# barGraph.net
KiCad netlist of a schematic drawn in Altium Designer
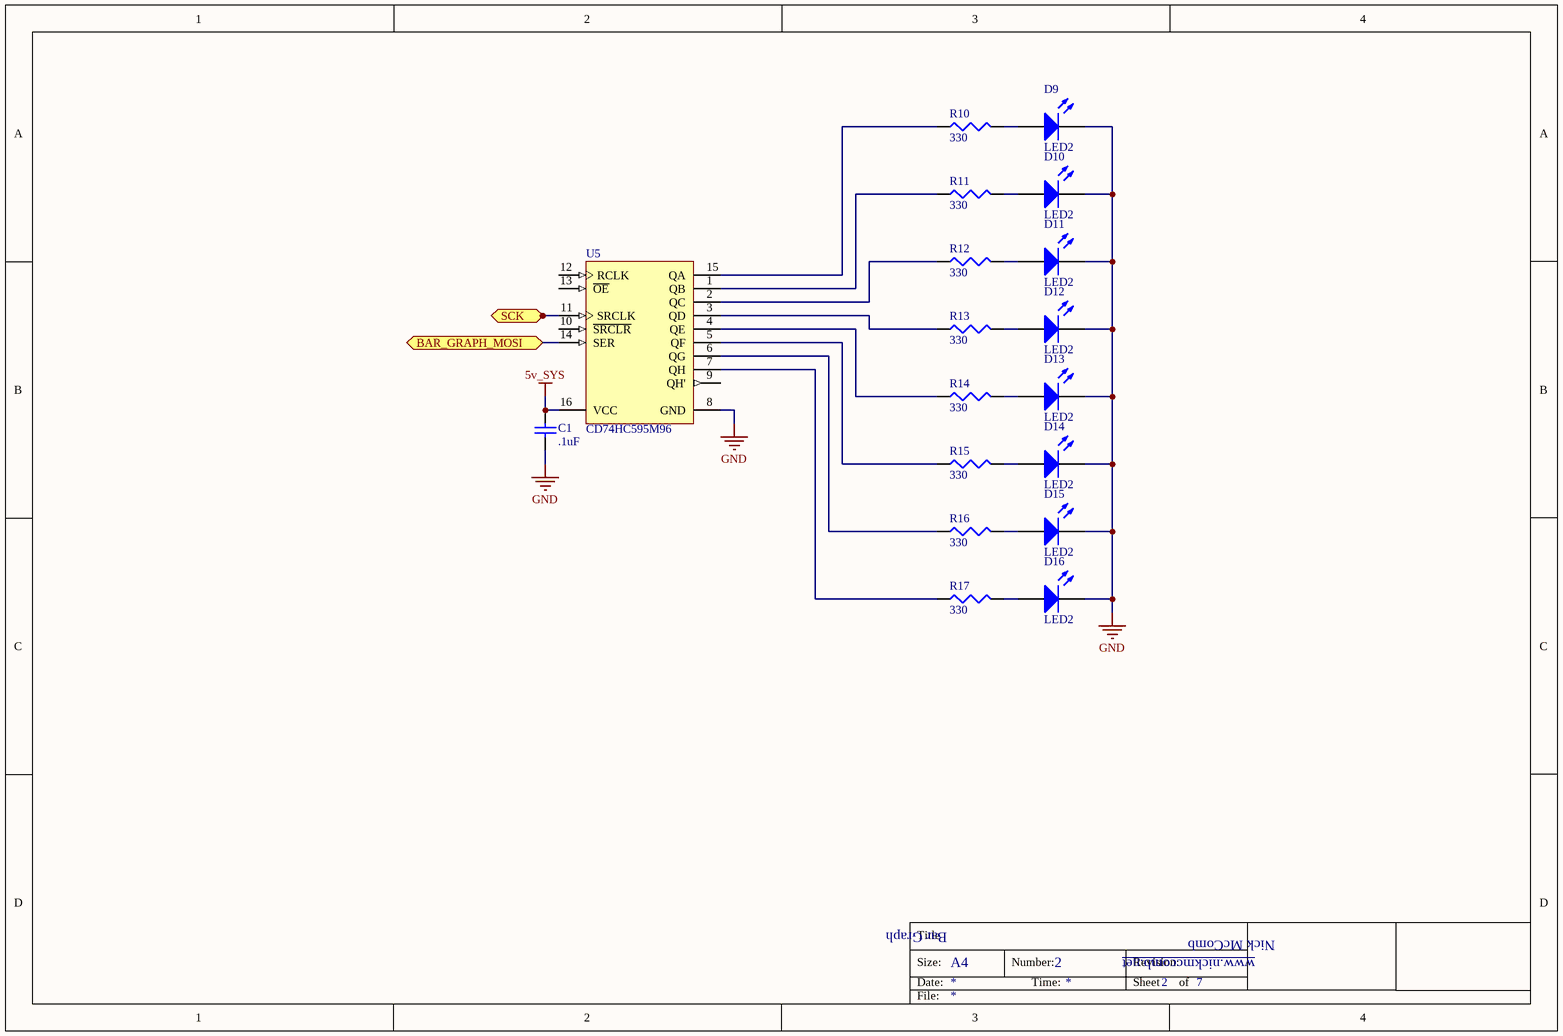
[diagram p0: barGraph.SchDoc]

(export (version "E")
  (design (tool "Eeschema 10.0.6"))
  (components
    (comp (ref "C1")
      (value ".1uF")
      (footprint "C0805")
      (description "Capacitor")
      (fields (field (name "Comment") "0805 style, by default") (field (name "PUBLISHER") "Altium Limited"))
      (libsource (lib "lab2") (part "Cap"))
    )
    (comp (ref "D9")
      (value "LED2")
      (footprint "basic_led")
      (description "Typical RED, GREEN, YELLOW, AMBER GaAs LED")
      (fields (field (name "PUBLISHER") "Altium Limited"))
      (libsource (lib "lab2") (part "LED2"))
    )
    (comp (ref "D10")
      (value "LED2")
      (footprint "basic_led")
      (description "Typical RED, GREEN, YELLOW, AMBER GaAs LED")
      (fields (field (name "PUBLISHER") "Altium Limited"))
      (libsource (lib "lab2") (part "LED2"))
    )
    (comp (ref "D11")
      (value "LED2")
      (footprint "basic_led")
      (description "Typical RED, GREEN, YELLOW, AMBER GaAs LED")
      (fields (field (name "PUBLISHER") "Altium Limited"))
      (libsource (lib "lab2") (part "LED2"))
    )
    (comp (ref "D12")
      (value "LED2")
      (footprint "basic_led")
      (description "Typical RED, GREEN, YELLOW, AMBER GaAs LED")
      (fields (field (name "PUBLISHER") "Altium Limited"))
      (libsource (lib "lab2") (part "LED2"))
    )
    (comp (ref "D13")
      (value "LED2")
      (footprint "basic_led")
      (description "Typical RED, GREEN, YELLOW, AMBER GaAs LED")
      (fields (field (name "PUBLISHER") "Altium Limited"))
      (libsource (lib "lab2") (part "LED2"))
    )
    (comp (ref "D14")
      (value "LED2")
      (footprint "basic_led")
      (description "Typical RED, GREEN, YELLOW, AMBER GaAs LED")
      (fields (field (name "PUBLISHER") "Altium Limited"))
      (libsource (lib "lab2") (part "LED2"))
    )
    (comp (ref "D15")
      (value "LED2")
      (footprint "basic_led")
      (description "Typical RED, GREEN, YELLOW, AMBER GaAs LED")
      (fields (field (name "PUBLISHER") "Altium Limited"))
      (libsource (lib "lab2") (part "LED2"))
    )
    (comp (ref "D16")
      (value "LED2")
      (footprint "basic_led")
      (description "Typical RED, GREEN, YELLOW, AMBER GaAs LED")
      (fields (field (name "PUBLISHER") "Altium Limited"))
      (libsource (lib "lab2") (part "LED2"))
    )
    (comp (ref "R10")
      (value "330")
      (footprint "J1-0603")
      (description "Resistor")
      (fields (field (name "PUBLISHER") "Altium Limited"))
      (libsource (lib "lab2") (part "Res3"))
    )
    (comp (ref "R11")
      (value "330")
      (footprint "J1-0603")
      (description "Resistor")
      (fields (field (name "PUBLISHER") "Altium Limited"))
      (libsource (lib "lab2") (part "Res3"))
    )
    (comp (ref "R12")
      (value "330")
      (footprint "J1-0603")
      (description "Resistor")
      (fields (field (name "PUBLISHER") "Altium Limited"))
      (libsource (lib "lab2") (part "Res3"))
    )
    (comp (ref "R13")
      (value "330")
      (footprint "J1-0603")
      (description "Resistor")
      (fields (field (name "PUBLISHER") "Altium Limited"))
      (libsource (lib "lab2") (part "Res3"))
    )
    (comp (ref "R14")
      (value "330")
      (footprint "J1-0603")
      (description "Resistor")
      (fields (field (name "PUBLISHER") "Altium Limited"))
      (libsource (lib "lab2") (part "Res3"))
    )
    (comp (ref "R15")
      (value "330")
      (footprint "J1-0603")
      (description "Resistor")
      (fields (field (name "PUBLISHER") "Altium Limited"))
      (libsource (lib "lab2") (part "Res3"))
    )
    (comp (ref "R16")
      (value "330")
      (footprint "J1-0603")
      (description "Resistor")
      (fields (field (name "PUBLISHER") "Altium Limited"))
      (libsource (lib "lab2") (part "Res3"))
    )
    (comp (ref "R17")
      (value "330")
      (footprint "J1-0603")
      (description "Resistor")
      (fields (field (name "PUBLISHER") "Altium Limited"))
      (libsource (lib "lab2") (part "Res3"))
    )
    (comp (ref "U5")
      (value "CD74HC595M96")
      (footprint "D0016A_L")
      (description "8-Bit Shift Registers With 3-State Output Registers, D0016A, LARGE T&R")
      (fields (field (name "PART NUMBER") "CD74HC595"))
      (libsource (lib "Altium Content Vault") (part "TI-CD74HC595-16"))
    )
  )
  (nets
    (net (code "1") (name "/BAR_GRAPH_MOSI") (class "Default")
      (node (ref "U5") (pin "14") (pinfunction "SER_14") (pintype "input"))
    )
    (net (code "2") (name "/SCK") (class "Default")
      (node (ref "U5") (pin "11") (pinfunction "SRCLK_11") (pintype "input"))
    )
    (net (code "3") (name "5v_SYS") (class "Default")
      (node (ref "C1") (pin "2") (pinfunction "2_2") (pintype "passive"))
      (node (ref "U5") (pin "16") (pinfunction "VCC_16") (pintype "power_in"))
    )
    (net (code "4") (name "GND") (class "Default")
      (node (ref "C1") (pin "1") (pinfunction "1_1") (pintype "passive"))
      (node (ref "D10") (pin "2") (pinfunction "K_2") (pintype "passive"))
      (node (ref "D11") (pin "2") (pinfunction "K_2") (pintype "passive"))
      (node (ref "D12") (pin "2") (pinfunction "K_2") (pintype "passive"))
      (node (ref "D13") (pin "2") (pinfunction "K_2") (pintype "passive"))
      (node (ref "D14") (pin "2") (pinfunction "K_2") (pintype "passive"))
      (node (ref "D15") (pin "2") (pinfunction "K_2") (pintype "passive"))
      (node (ref "D16") (pin "2") (pinfunction "K_2") (pintype "passive"))
      (node (ref "D9") (pin "2") (pinfunction "K_2") (pintype "passive"))
      (node (ref "U5") (pin "8") (pinfunction "GND_8") (pintype "power_in"))
    )
    (net (code "5") (name "Net-(D9-A)") (class "Default")
      (node (ref "D9") (pin "1") (pinfunction "A_1") (pintype "passive"))
      (node (ref "R10") (pin "2") (pinfunction "2_2") (pintype "passive"))
    )
    (net (code "6") (name "Net-(D10-A)") (class "Default")
      (node (ref "D10") (pin "1") (pinfunction "A_1") (pintype "passive"))
      (node (ref "R11") (pin "2") (pinfunction "2_2") (pintype "passive"))
    )
    (net (code "7") (name "Net-(D11-A)") (class "Default")
      (node (ref "D11") (pin "1") (pinfunction "A_1") (pintype "passive"))
      (node (ref "R12") (pin "2") (pinfunction "2_2") (pintype "passive"))
    )
    (net (code "8") (name "Net-(D12-A)") (class "Default")
      (node (ref "D12") (pin "1") (pinfunction "A_1") (pintype "passive"))
      (node (ref "R13") (pin "2") (pinfunction "2_2") (pintype "passive"))
    )
    (net (code "9") (name "Net-(D13-A)") (class "Default")
      (node (ref "D13") (pin "1") (pinfunction "A_1") (pintype "passive"))
      (node (ref "R14") (pin "2") (pinfunction "2_2") (pintype "passive"))
    )
    (net (code "10") (name "Net-(D14-A)") (class "Default")
      (node (ref "D14") (pin "1") (pinfunction "A_1") (pintype "passive"))
      (node (ref "R15") (pin "2") (pinfunction "2_2") (pintype "passive"))
    )
    (net (code "11") (name "Net-(D15-A)") (class "Default")
      (node (ref "D15") (pin "1") (pinfunction "A_1") (pintype "passive"))
      (node (ref "R16") (pin "2") (pinfunction "2_2") (pintype "passive"))
    )
    (net (code "12") (name "Net-(D16-A)") (class "Default")
      (node (ref "D16") (pin "1") (pinfunction "A_1") (pintype "passive"))
      (node (ref "R17") (pin "2") (pinfunction "2_2") (pintype "passive"))
    )
    (net (code "13") (name "Net-(U5-QA)") (class "Default")
      (node (ref "R10") (pin "1") (pinfunction "1_1") (pintype "passive"))
      (node (ref "U5") (pin "15") (pinfunction "QA_15") (pintype "tri_state"))
    )
    (net (code "14") (name "Net-(U5-QB)") (class "Default")
      (node (ref "R11") (pin "1") (pinfunction "1_1") (pintype "passive"))
      (node (ref "U5") (pin "1") (pinfunction "QB_1") (pintype "tri_state"))
    )
    (net (code "15") (name "Net-(U5-QC)") (class "Default")
      (node (ref "R12") (pin "1") (pinfunction "1_1") (pintype "passive"))
      (node (ref "U5") (pin "2") (pinfunction "QC_2") (pintype "tri_state"))
    )
    (net (code "16") (name "Net-(U5-QD)") (class "Default")
      (node (ref "R13") (pin "1") (pinfunction "1_1") (pintype "passive"))
      (node (ref "U5") (pin "3") (pinfunction "QD_3") (pintype "tri_state"))
    )
    (net (code "17") (name "Net-(U5-QE)") (class "Default")
      (node (ref "R14") (pin "1") (pinfunction "1_1") (pintype "passive"))
      (node (ref "U5") (pin "4") (pinfunction "QE_4") (pintype "tri_state"))
    )
    (net (code "18") (name "Net-(U5-QF)") (class "Default")
      (node (ref "R15") (pin "1") (pinfunction "1_1") (pintype "passive"))
      (node (ref "U5") (pin "5") (pinfunction "QF_5") (pintype "tri_state"))
    )
    (net (code "19") (name "Net-(U5-QG)") (class "Default")
      (node (ref "R16") (pin "1") (pinfunction "1_1") (pintype "passive"))
      (node (ref "U5") (pin "6") (pinfunction "QG_6") (pintype "tri_state"))
    )
    (net (code "20") (name "Net-(U5-QH)") (class "Default")
      (node (ref "R17") (pin "1") (pinfunction "1_1") (pintype "passive"))
      (node (ref "U5") (pin "7") (pinfunction "QH_7") (pintype "tri_state"))
    )
    (net (code "21") (name "unconnected-(U5-QH'-Pad9)") (class "Default")
      (node (ref "U5") (pin "9") (pinfunction "QH'_9") (pintype "output"))
    )
    (net (code "22") (name "unconnected-(U5-RCLK-Pad12)") (class "Default")
      (node (ref "U5") (pin "12") (pinfunction "RCLK_12") (pintype "input"))
    )
    (net (code "23") (name "unconnected-(U5-~{OE}-Pad13)") (class "Default")
      (node (ref "U5") (pin "13") (pinfunction "~{OE}_13") (pintype "input"))
    )
    (net (code "24") (name "unconnected-(U5-~{SRCLR}-Pad10)") (class "Default")
      (node (ref "U5") (pin "10") (pinfunction "~{SRCLR}_10") (pintype "input"))
    )
  )
)
